# config.net
KiCad netlist of a schematic drawn in EAGLE
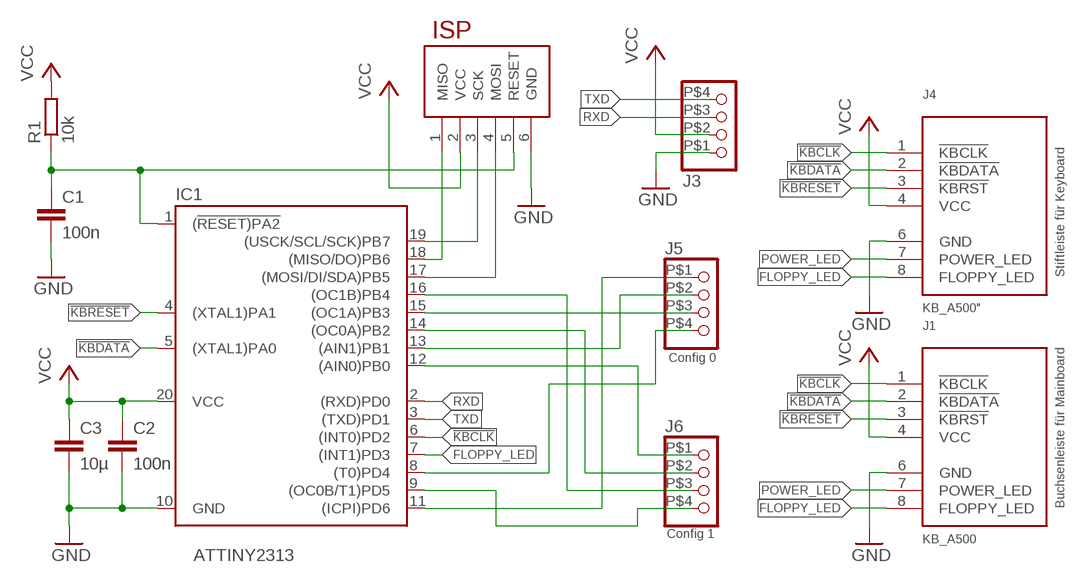
[diagram p0: schematic, sheet 1]

(export (version "E")
  (design (tool "Eeschema 10.0.6"))
  (components
    (comp (ref "C1")
      (value "100n")
      (footprint "eagle-import:C0805")
      (libsource (lib "eagle-import") (part "C-EUC0805"))
    )
    (comp (ref "C2")
      (value "100n")
      (footprint "eagle-import:C0805")
      (libsource (lib "eagle-import") (part "C-EUC0805"))
    )
    (comp (ref "C3")
      (value "10µ")
      (footprint "eagle-import:C1206")
      (libsource (lib "eagle-import") (part "C-EUC1206"))
    )
    (comp (ref "IC1")
      (value "ATTINY2313")
      (footprint "eagle-import:SO20L")
      (libsource (lib "eagle-import") (part "ATTINY2313"))
    )
    (comp (ref "J1")
      (value "KB_A500")
      (footprint "eagle-import:1X08S")
      (libsource (lib "eagle-import") (part "KB_A500"))
    )
    (comp (ref "J2")
      (value "ISP")
      (footprint "eagle-import:2X03")
      (libsource (lib "eagle-import") (part "ISP6STEHEND"))
    )
    (comp (ref "J3")
      (value "PINHD-1X4")
      (footprint "eagle-import:1X04SLIM")
      (libsource (lib "eagle-import") (part "PINHD-1X4"))
    )
    (comp (ref "J4")
      (value "KB_A500\"")
      (footprint "eagle-import:1X08_90SLIM")
      (libsource (lib "eagle-import") (part "KB_A500{dblquote}"))
    )
    (comp (ref "J5")
      (value "PINHD-1X4")
      (footprint "eagle-import:1X04SLIM")
      (libsource (lib "eagle-import") (part "PINHD-1X4"))
    )
    (comp (ref "J6")
      (value "PINHD-1X4")
      (footprint "eagle-import:1X04SLIM")
      (libsource (lib "eagle-import") (part "PINHD-1X4"))
    )
    (comp (ref "R1")
      (value "10k")
      (footprint "eagle-import:R0805")
      (libsource (lib "eagle-import") (part "R-EU_R0805"))
    )
  )
  (nets
    (net (code "1") (name "/~{KBCLK}") (class "Default")
      (node (ref "IC1") (pin "6") (pinfunction "(INT0)PD2_6") (pintype "bidirectional"))
      (node (ref "J1") (pin "1") (pinfunction "~{KBCLK}_1") (pintype "bidirectional"))
      (node (ref "J4") (pin "1") (pinfunction "~{KBCLK}_1") (pintype "bidirectional"))
    )
    (net (code "2") (name "/~{KBDATA}") (class "Default")
      (node (ref "IC1") (pin "5") (pinfunction "(XTAL1)PA0_5") (pintype "bidirectional"))
      (node (ref "J1") (pin "2") (pinfunction "~{KBDATA}_2") (pintype "bidirectional"))
      (node (ref "J4") (pin "2") (pinfunction "~{KBDATA}_2") (pintype "bidirectional"))
    )
    (net (code "3") (name "/~{KBRESET}") (class "Default")
      (node (ref "IC1") (pin "4") (pinfunction "(XTAL1)PA1_4") (pintype "bidirectional"))
      (node (ref "J1") (pin "3") (pinfunction "~{KBRST}_3") (pintype "bidirectional"))
      (node (ref "J4") (pin "3") (pinfunction "~{KBRST}_3") (pintype "bidirectional"))
    )
    (net (code "4") (name "FLOPPY_LED") (class "Default")
      (node (ref "IC1") (pin "7") (pinfunction "(INT1)PD3_7") (pintype "bidirectional"))
      (node (ref "J1") (pin "8") (pinfunction "FLOPPY_LED_8") (pintype "input"))
      (node (ref "J4") (pin "8") (pinfunction "FLOPPY_LED_8") (pintype "input"))
    )
    (net (code "5") (name "GND") (class "Default")
      (node (ref "C1") (pin "2") (pinfunction "2_2") (pintype "passive"))
      (node (ref "C2") (pin "2") (pinfunction "2_2") (pintype "passive"))
      (node (ref "C3") (pin "2") (pinfunction "2_2") (pintype "passive"))
      (node (ref "IC1") (pin "10") (pinfunction "GND_10") (pintype "power_in"))
      (node (ref "J1") (pin "6") (pinfunction "GND_6") (pintype "power_in"))
      (node (ref "J2") (pin "6") (pinfunction "GND_6") (pintype "bidirectional"))
      (node (ref "J3") (pin "P$1") (pinfunction "1_P$1") (pintype "passive"))
      (node (ref "J4") (pin "6") (pinfunction "GND_6") (pintype "power_in"))
    )
    (net (code "6") (name "Net-(IC1-(AIN0)PB0)") (class "Default")
      (node (ref "IC1") (pin "12") (pinfunction "(AIN0)PB0_12") (pintype "bidirectional"))
      (node (ref "J6") (pin "P$1") (pinfunction "1_P$1") (pintype "passive"))
    )
    (net (code "7") (name "Net-(IC1-(AIN1)PB1)") (class "Default")
      (node (ref "IC1") (pin "13") (pinfunction "(AIN1)PB1_13") (pintype "bidirectional"))
      (node (ref "J5") (pin "P$2") (pinfunction "2_P$2") (pintype "passive"))
    )
    (net (code "8") (name "Net-(IC1-(ICPI)PD6)") (class "Default")
      (node (ref "IC1") (pin "11") (pinfunction "(ICPI)PD6_11") (pintype "bidirectional"))
      (node (ref "J5") (pin "P$1") (pinfunction "1_P$1") (pintype "passive"))
    )
    (net (code "9") (name "Net-(IC1-(MISO{slash}DO)PB6)") (class "Default")
      (node (ref "IC1") (pin "18") (pinfunction "(MISO/DO)PB6_18") (pintype "bidirectional"))
      (node (ref "J2") (pin "1") (pinfunction "MISO_1") (pintype "bidirectional"))
    )
    (net (code "10") (name "Net-(IC1-(MOSI{slash}DI{slash}SDA)PB5)") (class "Default")
      (node (ref "IC1") (pin "17") (pinfunction "(MOSI/DI/SDA)PB5_17") (pintype "bidirectional"))
      (node (ref "J2") (pin "4") (pinfunction "MOSI_4") (pintype "bidirectional"))
    )
    (net (code "11") (name "Net-(IC1-(OC0A)PB2)") (class "Default")
      (node (ref "IC1") (pin "14") (pinfunction "(OC0A)PB2_14") (pintype "bidirectional"))
      (node (ref "J6") (pin "P$2") (pinfunction "2_P$2") (pintype "passive"))
    )
    (net (code "12") (name "Net-(IC1-(OC0B{slash}T1)PD5)") (class "Default")
      (node (ref "IC1") (pin "9") (pinfunction "(OC0B/T1)PD5_9") (pintype "bidirectional"))
      (node (ref "J6") (pin "P$4") (pinfunction "4_P$4") (pintype "passive"))
    )
    (net (code "13") (name "Net-(IC1-(OC1A)PB3)") (class "Default")
      (node (ref "IC1") (pin "15") (pinfunction "(OC1A)PB3_15") (pintype "bidirectional"))
      (node (ref "J5") (pin "P$3") (pinfunction "3_P$3") (pintype "passive"))
    )
    (net (code "14") (name "Net-(IC1-(OC1B)PB4)") (class "Default")
      (node (ref "IC1") (pin "16") (pinfunction "(OC1B)PB4_16") (pintype "bidirectional"))
      (node (ref "J6") (pin "P$3") (pinfunction "3_P$3") (pintype "passive"))
    )
    (net (code "15") (name "Net-(IC1-(T0)PD4)") (class "Default")
      (node (ref "IC1") (pin "8") (pinfunction "(T0)PD4_8") (pintype "bidirectional"))
      (node (ref "J5") (pin "P$4") (pinfunction "4_P$4") (pintype "passive"))
    )
    (net (code "16") (name "Net-(IC1-(USCK{slash}SCL{slash}SCK)PB7)") (class "Default")
      (node (ref "IC1") (pin "19") (pinfunction "(USCK/SCL/SCK)PB7_19") (pintype "bidirectional"))
      (node (ref "J2") (pin "3") (pinfunction "SCK_3") (pintype "bidirectional"))
    )
    (net (code "17") (name "Net-(IC1-(~{RESET})PA2)") (class "Default")
      (node (ref "C1") (pin "1") (pinfunction "1_1") (pintype "passive"))
      (node (ref "IC1") (pin "1") (pinfunction "(~{RESET})PA2_1") (pintype "bidirectional"))
      (node (ref "J2") (pin "5") (pinfunction "RESET_5") (pintype "bidirectional"))
      (node (ref "R1") (pin "1") (pinfunction "1_1") (pintype "passive"))
    )
    (net (code "18") (name "POWER_LED") (class "Default")
      (node (ref "J1") (pin "7") (pinfunction "POWER_LED_7") (pintype "input"))
      (node (ref "J4") (pin "7") (pinfunction "POWER_LED_7") (pintype "input"))
    )
    (net (code "19") (name "RXD") (class "Default")
      (node (ref "IC1") (pin "2") (pinfunction "(RXD)PD0_2") (pintype "bidirectional"))
      (node (ref "J3") (pin "P$3") (pinfunction "3_P$3") (pintype "passive"))
    )
    (net (code "20") (name "TXD") (class "Default")
      (node (ref "IC1") (pin "3") (pinfunction "(TXD)PD1_3") (pintype "bidirectional"))
      (node (ref "J3") (pin "P$4") (pinfunction "4_P$4") (pintype "passive"))
    )
    (net (code "21") (name "VCC") (class "Default")
      (node (ref "C2") (pin "1") (pinfunction "1_1") (pintype "passive"))
      (node (ref "C3") (pin "1") (pinfunction "1_1") (pintype "passive"))
      (node (ref "IC1") (pin "20") (pinfunction "VCC_20") (pintype "power_in"))
      (node (ref "J1") (pin "4") (pinfunction "VCC_4") (pintype "power_in"))
      (node (ref "J2") (pin "2") (pinfunction "VCC_2") (pintype "bidirectional"))
      (node (ref "J3") (pin "P$2") (pinfunction "2_P$2") (pintype "passive"))
      (node (ref "J4") (pin "4") (pinfunction "VCC_4") (pintype "power_in"))
      (node (ref "R1") (pin "2") (pinfunction "2_2") (pintype "passive"))
    )
  )
)
